# design.net
KiCad netlist of a schematic drawn in Altium Designer
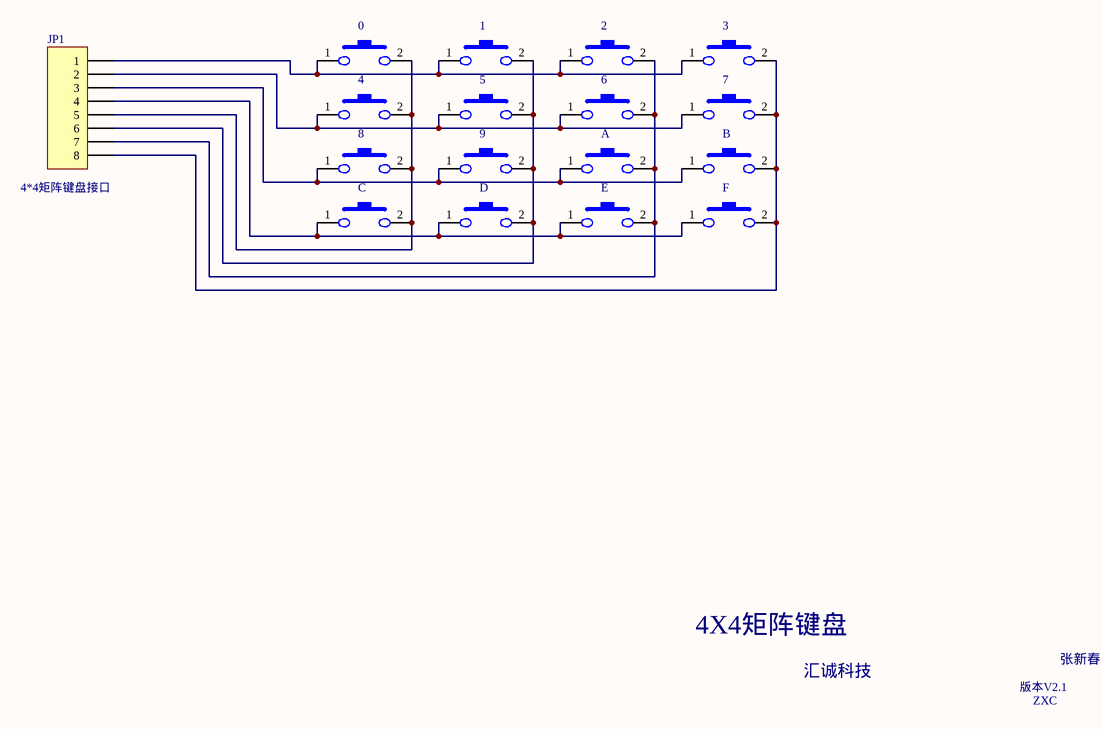
[diagram p0: 矩阵键盘.SchDoc]

(export (version "E")
  (design (tool "Eeschema 10.0.6"))
  (components
    (comp (ref "0") (value "key1") (footprint "an-6*6") (libsource (lib "OldCow1 (1)") (part "key")))
    (comp (ref "1") (value "key1") (footprint "an-6*6") (libsource (lib "OldCow1 (1)") (part "key")))
    (comp (ref "2") (value "key1") (footprint "an-6*6") (libsource (lib "OldCow1 (1)") (part "key")))
    (comp (ref "3") (value "key1") (footprint "an-6*6") (libsource (lib "OldCow1 (1)") (part "key")))
    (comp (ref "4") (value "key2") (footprint "an-6*6") (libsource (lib "OldCow1 (1)") (part "key")))
    (comp (ref "5") (value "key2") (footprint "an-6*6") (libsource (lib "OldCow1 (1)") (part "key")))
    (comp (ref "6") (value "key2") (footprint "an-6*6") (libsource (lib "OldCow1 (1)") (part "key")))
    (comp (ref "7") (value "key2") (footprint "an-6*6") (libsource (lib "OldCow1 (1)") (part "key")))
    (comp (ref "8") (value "key3") (footprint "an-6*6") (libsource (lib "OldCow1 (1)") (part "key")))
    (comp (ref "9") (value "key3") (footprint "an-6*6") (libsource (lib "OldCow1 (1)") (part "key")))
    (comp (ref "A") (value "key3") (footprint "an-6*6") (libsource (lib "OldCow1 (1)") (part "key")))
    (comp (ref "B") (value "key3") (footprint "an-6*6") (libsource (lib "OldCow1 (1)") (part "key")))
    (comp (ref "C") (value "key4") (footprint "an-6*6") (libsource (lib "OldCow1 (1)") (part "key")))
    (comp (ref "D") (value "key4") (footprint "an-6*6") (libsource (lib "OldCow1 (1)") (part "key")))
    (comp (ref "E") (value "key4") (footprint "an-6*6") (libsource (lib "OldCow1 (1)") (part "key")))
    (comp (ref "F") (value "key4") (footprint "an-6*6") (libsource (lib "OldCow1 (1)") (part "key")))
    (comp (ref "JP1")
      (value "4*4矩阵键盘接口")
      (footprint "HDR1X8")
      (description "Header, 8-Pin")
      (fields (field (name "PUBLISHER") "Altium Limited"))
      (libsource (lib "Miscellaneous Connectors") (part "Header 8"))
    )
  )
  (nets
    (net (code "1") (name "Net-(0-Pad1)") (class "Default")
      (node (ref "0") (pin "1") (pinfunction "1_1") (pintype "passive"))
      (node (ref "1") (pin "1") (pinfunction "1_1") (pintype "passive"))
      (node (ref "2") (pin "1") (pinfunction "1_1") (pintype "passive"))
      (node (ref "3") (pin "1") (pinfunction "1_1") (pintype "passive"))
      (node (ref "JP1") (pin "1") (pinfunction "1_1") (pintype "passive"))
    )
    (net (code "2") (name "Net-(0-Pad2)") (class "Default")
      (node (ref "0") (pin "2") (pinfunction "2_2") (pintype "passive"))
      (node (ref "4") (pin "2") (pinfunction "2_2") (pintype "passive"))
      (node (ref "8") (pin "2") (pinfunction "2_2") (pintype "passive"))
      (node (ref "C") (pin "2") (pinfunction "2_2") (pintype "passive"))
      (node (ref "JP1") (pin "5") (pinfunction "5_5") (pintype "passive"))
    )
    (net (code "3") (name "Net-(1-Pad2)") (class "Default")
      (node (ref "1") (pin "2") (pinfunction "2_2") (pintype "passive"))
      (node (ref "5") (pin "2") (pinfunction "2_2") (pintype "passive"))
      (node (ref "9") (pin "2") (pinfunction "2_2") (pintype "passive"))
      (node (ref "D") (pin "2") (pinfunction "2_2") (pintype "passive"))
      (node (ref "JP1") (pin "6") (pinfunction "6_6") (pintype "passive"))
    )
    (net (code "4") (name "Net-(2-Pad2)") (class "Default")
      (node (ref "2") (pin "2") (pinfunction "2_2") (pintype "passive"))
      (node (ref "6") (pin "2") (pinfunction "2_2") (pintype "passive"))
      (node (ref "A") (pin "2") (pinfunction "2_2") (pintype "passive"))
      (node (ref "E") (pin "2") (pinfunction "2_2") (pintype "passive"))
      (node (ref "JP1") (pin "7") (pinfunction "7_7") (pintype "passive"))
    )
    (net (code "5") (name "Net-(3-Pad2)") (class "Default")
      (node (ref "3") (pin "2") (pinfunction "2_2") (pintype "passive"))
      (node (ref "7") (pin "2") (pinfunction "2_2") (pintype "passive"))
      (node (ref "B") (pin "2") (pinfunction "2_2") (pintype "passive"))
      (node (ref "F") (pin "2") (pinfunction "2_2") (pintype "passive"))
      (node (ref "JP1") (pin "8") (pinfunction "8_8") (pintype "passive"))
    )
    (net (code "6") (name "Net-(4-Pad1)") (class "Default")
      (node (ref "4") (pin "1") (pinfunction "1_1") (pintype "passive"))
      (node (ref "5") (pin "1") (pinfunction "1_1") (pintype "passive"))
      (node (ref "6") (pin "1") (pinfunction "1_1") (pintype "passive"))
      (node (ref "7") (pin "1") (pinfunction "1_1") (pintype "passive"))
      (node (ref "JP1") (pin "2") (pinfunction "2_2") (pintype "passive"))
    )
    (net (code "7") (name "Net-(8-Pad1)") (class "Default")
      (node (ref "8") (pin "1") (pinfunction "1_1") (pintype "passive"))
      (node (ref "9") (pin "1") (pinfunction "1_1") (pintype "passive"))
      (node (ref "A") (pin "1") (pinfunction "1_1") (pintype "passive"))
      (node (ref "B") (pin "1") (pinfunction "1_1") (pintype "passive"))
      (node (ref "JP1") (pin "3") (pinfunction "3_3") (pintype "passive"))
    )
    (net (code "8") (name "Net-(C-Pad1)") (class "Default")
      (node (ref "C") (pin "1") (pinfunction "1_1") (pintype "passive"))
      (node (ref "D") (pin "1") (pinfunction "1_1") (pintype "passive"))
      (node (ref "E") (pin "1") (pinfunction "1_1") (pintype "passive"))
      (node (ref "F") (pin "1") (pinfunction "1_1") (pintype "passive"))
      (node (ref "JP1") (pin "4") (pinfunction "4_4") (pintype "passive"))
    )
  )
)
